# control.net
KiCad netlist of a schematic drawn in EAGLE
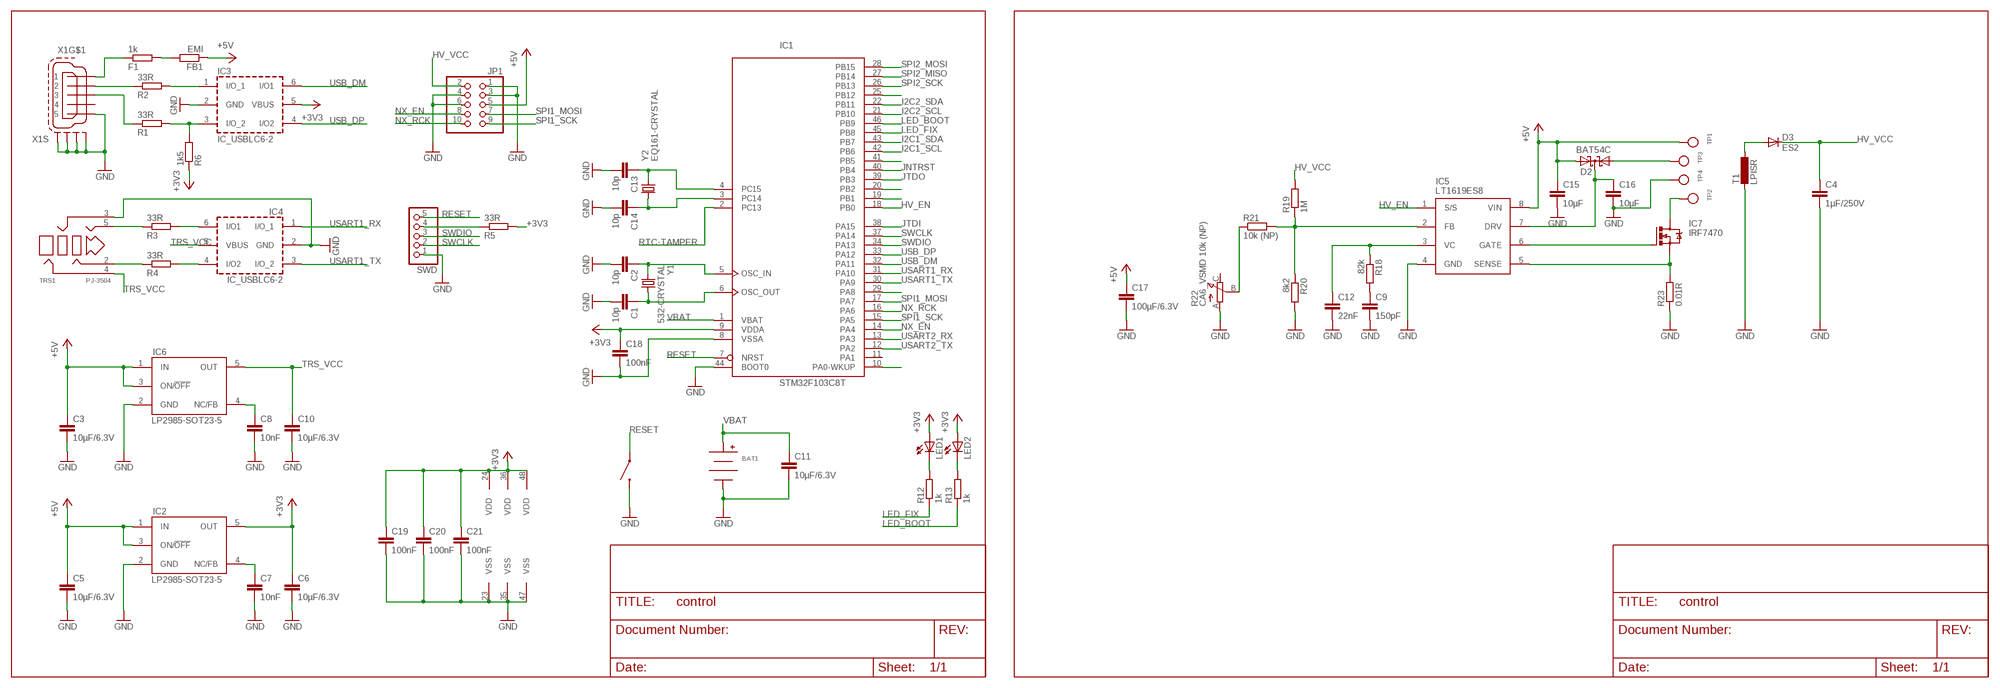
[diagram p0: schematic, sheet 1]

(export (version "E")
  (design (tool "Eeschema 10.0.6"))
  (components
    (comp (ref "BAT1")
      (value "CR1220-HOLDER")
      (footprint "eagle-import:HARWIN-CR1220")
      (libsource (lib "eagle-import") (part "CR1220-HOLDER"))
    )
    (comp (ref "C1")
      (value "10p")
      (footprint "eagle-import:C0603")
      (libsource (lib "eagle-import") (part "C-EUC0603"))
    )
    (comp (ref "C2")
      (value "10p")
      (footprint "eagle-import:C0603")
      (libsource (lib "eagle-import") (part "C-EUC0603"))
    )
    (comp (ref "C3")
      (value "10µF/6.3V")
      (footprint "eagle-import:C0603")
      (libsource (lib "eagle-import") (part "C-EUC0603"))
    )
    (comp (ref "C4")
      (value "1µF/250V")
      (footprint "eagle-import:C2220K")
      (libsource (lib "eagle-import") (part "C-EUC2220K"))
    )
    (comp (ref "C5")
      (value "10µF/6.3V")
      (footprint "eagle-import:C0603")
      (libsource (lib "eagle-import") (part "C-EUC0603"))
    )
    (comp (ref "C6")
      (value "10µF/6.3V")
      (footprint "eagle-import:C0603")
      (libsource (lib "eagle-import") (part "C-EUC0603"))
    )
    (comp (ref "C7")
      (value "10nF")
      (footprint "eagle-import:C0603")
      (libsource (lib "eagle-import") (part "C-EUC0603"))
    )
    (comp (ref "C8")
      (value "10nF")
      (footprint "eagle-import:C0603")
      (libsource (lib "eagle-import") (part "C-EUC0603"))
    )
    (comp (ref "C9")
      (value "150pF")
      (footprint "eagle-import:C0603")
      (libsource (lib "eagle-import") (part "C-EUC0603"))
    )
    (comp (ref "C10")
      (value "10µF/6.3V")
      (footprint "eagle-import:C0603")
      (libsource (lib "eagle-import") (part "C-EUC0603"))
    )
    (comp (ref "C11")
      (value "10µF/6.3V")
      (footprint "eagle-import:C0603")
      (libsource (lib "eagle-import") (part "C-EUC0603"))
    )
    (comp (ref "C12")
      (value "22nF")
      (footprint "eagle-import:C0603")
      (libsource (lib "eagle-import") (part "C-EUC0603"))
    )
    (comp (ref "C13")
      (value "10p")
      (footprint "eagle-import:C0603")
      (libsource (lib "eagle-import") (part "C-EUC0603"))
    )
    (comp (ref "C14")
      (value "10p")
      (footprint "eagle-import:C0603")
      (libsource (lib "eagle-import") (part "C-EUC0603"))
    )
    (comp (ref "C15")
      (value "10µF")
      (footprint "eagle-import:C0603")
      (libsource (lib "eagle-import") (part "C-EUC0603"))
    )
    (comp (ref "C16")
      (value "10µF")
      (footprint "eagle-import:C0603")
      (libsource (lib "eagle-import") (part "C-EUC0603"))
    )
    (comp (ref "C17")
      (value "100µF/6.3V")
      (footprint "eagle-import:C1210")
      (libsource (lib "eagle-import") (part "C-EUC1210"))
    )
    (comp (ref "C18")
      (value "100nF")
      (footprint "eagle-import:C0603")
      (libsource (lib "eagle-import") (part "C-EUC0603"))
    )
    (comp (ref "C19")
      (value "100nF")
      (footprint "eagle-import:C0603")
      (libsource (lib "eagle-import") (part "C-EUC0603"))
    )
    (comp (ref "C20")
      (value "100nF")
      (footprint "eagle-import:C0603")
      (libsource (lib "eagle-import") (part "C-EUC0603"))
    )
    (comp (ref "C21")
      (value "100nF")
      (footprint "eagle-import:C0603")
      (libsource (lib "eagle-import") (part "C-EUC0603"))
    )
    (comp (ref "D2")
      (value "BAT54C")
      (footprint "eagle-import:SOT23")
      (libsource (lib "eagle-import") (part "BAT54C"))
    )
    (comp (ref "D3")
      (value "ES2")
      (footprint "eagle-import:DO-214AA")
      (libsource (lib "eagle-import") (part "ES2"))
    )
    (comp (ref "F1")
      (value "1k")
      (footprint "eagle-import:R0603")
      (libsource (lib "eagle-import") (part "R-EU_R0603"))
    )
    (comp (ref "FB1")
      (value "EMI")
      (footprint "eagle-import:R0603")
      (libsource (lib "eagle-import") (part "R-EU_R0603"))
    )
    (comp (ref "IC1")
      (value "STM32F103C8T")
      (footprint "eagle-import:LQFP48")
      (libsource (lib "eagle-import") (part "STM32F103CT8"))
    )
    (comp (ref "IC2")
      (value "LP2985-SOT23-5")
      (footprint "eagle-import:SOT23-5")
      (libsource (lib "eagle-import") (part "LP2985-SOT23-5"))
    )
    (comp (ref "IC3")
      (value "IC_USBLC6-2")
      (footprint "eagle-import:SOT-23-6L")
      (libsource (lib "eagle-import") (part "IC_USBLC6-2"))
    )
    (comp (ref "IC4")
      (value "IC_USBLC6-2")
      (footprint "eagle-import:SOT-23-6L")
      (libsource (lib "eagle-import") (part "IC_USBLC6-2"))
    )
    (comp (ref "IC5")
      (value "LT1619ES8")
      (footprint "eagle-import:SO8")
      (libsource (lib "eagle-import") (part "LT1619ES8"))
    )
    (comp (ref "IC6")
      (value "LP2985-SOT23-5")
      (footprint "eagle-import:SOT23-5")
      (libsource (lib "eagle-import") (part "LP2985-SOT23-5"))
    )
    (comp (ref "IC7")
      (value "IRF7470")
      (footprint "eagle-import:SO8")
      (libsource (lib "eagle-import") (part "IRF7470"))
    )
    (comp (ref "ISP")
      (value "TACT-SWITCH-40-40")
      (footprint "eagle-import:40-40")
      (libsource (lib "eagle-import") (part "TACT-SWITCH-40-40"))
    )
    (comp (ref "JP1")
      (value "PINHD-2X5_2.54-SMD")
      (footprint "eagle-import:2X05SMD")
      (libsource (lib "eagle-import") (part "PINHD-2X5_2.54-SMD"))
    )
    (comp (ref "LED1")
      (value "LEDCHIP-LED0603")
      (footprint "eagle-import:CHIP-LED0603")
      (libsource (lib "eagle-import") (part "LEDCHIP-LED0603"))
    )
    (comp (ref "LED2")
      (value "LEDCHIP-LED0603")
      (footprint "eagle-import:CHIP-LED0603")
      (libsource (lib "eagle-import") (part "LEDCHIP-LED0603"))
    )
    (comp (ref "R1")
      (value "33R")
      (footprint "eagle-import:R0603")
      (libsource (lib "eagle-import") (part "R-EU_R0603"))
    )
    (comp (ref "R2")
      (value "33R")
      (footprint "eagle-import:R0603")
      (libsource (lib "eagle-import") (part "R-EU_R0603"))
    )
    (comp (ref "R3")
      (value "33R")
      (footprint "eagle-import:R0603")
      (libsource (lib "eagle-import") (part "R-EU_R0603"))
    )
    (comp (ref "R4")
      (value "33R")
      (footprint "eagle-import:R0603")
      (libsource (lib "eagle-import") (part "R-EU_R0603"))
    )
    (comp (ref "R5")
      (value "33R")
      (footprint "eagle-import:R0603")
      (libsource (lib "eagle-import") (part "R-EU_R0603"))
    )
    (comp (ref "R6")
      (value "1k5")
      (footprint "eagle-import:R0603")
      (libsource (lib "eagle-import") (part "R-EU_R0603"))
    )
    (comp (ref "R12")
      (value "1k")
      (footprint "eagle-import:R0603")
      (libsource (lib "eagle-import") (part "R-EU_R0603"))
    )
    (comp (ref "R13")
      (value "1k")
      (footprint "eagle-import:R0603")
      (libsource (lib "eagle-import") (part "R-EU_R0603"))
    )
    (comp (ref "R18")
      (value "82k")
      (footprint "eagle-import:R0603")
      (libsource (lib "eagle-import") (part "R-EU_R0603"))
    )
    (comp (ref "R19")
      (value "1M")
      (footprint "eagle-import:M1206")
      (libsource (lib "eagle-import") (part "R-EU_M1206"))
    )
    (comp (ref "R20")
      (value "8k2")
      (footprint "eagle-import:R0603")
      (libsource (lib "eagle-import") (part "R-EU_R0603"))
    )
    (comp (ref "R21")
      (value "10k (NP)")
      (footprint "eagle-import:R0603")
      (libsource (lib "eagle-import") (part "R-EU_R0603"))
    )
    (comp (ref "R22")
      (value "CA6_VSMD 10k (NP)")
      (footprint "eagle-import:CA6-VSMD")
      (libsource (lib "eagle-import") (part "CA6_VSMD"))
    )
    (comp (ref "R23")
      (value "0.01R")
      (footprint "eagle-import:R1206")
      (libsource (lib "eagle-import") (part "R-EU_R1206"))
    )
    (comp (ref "SWD")
      (value "HEADER-1X5ROUND")
      (footprint "eagle-import:1X05_ROUND")
      (libsource (lib "eagle-import") (part "HEADER-1X5ROUND"))
    )
    (comp (ref "T1")
      (value "LPISR")
      (footprint "eagle-import:PISR")
      (libsource (lib "eagle-import") (part "LPISR"))
    )
    (comp (ref "TP1")
      (value "TESTPOINTROUND2MM")
      (footprint "eagle-import:TESTPOINT_ROUND_2MM")
      (libsource (lib "eagle-import") (part "TESTPOINTROUND2MM"))
    )
    (comp (ref "TP2")
      (value "TESTPOINTROUND2MM")
      (footprint "eagle-import:TESTPOINT_ROUND_2MM")
      (libsource (lib "eagle-import") (part "TESTPOINTROUND2MM"))
    )
    (comp (ref "TP3")
      (value "TESTPOINTROUND2MM")
      (footprint "eagle-import:TESTPOINT_ROUND_2MM")
      (libsource (lib "eagle-import") (part "TESTPOINTROUND2MM"))
    )
    (comp (ref "TP4")
      (value "TESTPOINTROUND2MM")
      (footprint "eagle-import:TESTPOINT_ROUND_2MM")
      (libsource (lib "eagle-import") (part "TESTPOINTROUND2MM"))
    )
    (comp (ref "TRS1")
      (value "PJ-3504")
      (footprint "eagle-import:YD-PJ-3504")
      (libsource (lib "eagle-import") (part "PJ-3504"))
    )
    (comp (ref "X1")
      (value "MINI-USB-SCHIELD-32005-201")
      (footprint "eagle-import:32005-201")
      (libsource (lib "eagle-import") (part "MINI-USB-SCHIELD-32005-201"))
    )
    (comp (ref "Y1")
      (value "532-CRYSTAL")
      (footprint "eagle-import:2PIN50X32")
      (libsource (lib "eagle-import") (part "532-CRYSTAL"))
    )
    (comp (ref "Y2")
      (value "EQ161-CRYSTAL")
      (footprint "eagle-import:EQ161")
      (libsource (lib "eagle-import") (part "EQ161-CRYSTAL"))
    )
  )
  (nets
    (net (code "1") (name "+3V3") (class "Default")
      (node (ref "C18") (pin "1") (pinfunction "1_1") (pintype "passive"))
      (node (ref "C19") (pin "1") (pinfunction "1_1") (pintype "passive"))
      (node (ref "C20") (pin "1") (pinfunction "1_1") (pintype "passive"))
      (node (ref "C21") (pin "1") (pinfunction "1_1") (pintype "passive"))
      (node (ref "C6") (pin "1") (pinfunction "1_1") (pintype "passive"))
      (node (ref "IC1") (pin "24") (pinfunction "VDD_24") (pintype "power_in"))
      (node (ref "IC1") (pin "36") (pinfunction "VDD_36") (pintype "power_in"))
      (node (ref "IC1") (pin "48") (pinfunction "VDD_48") (pintype "power_in"))
      (node (ref "IC1") (pin "9") (pinfunction "VDDA_9") (pintype "power_in"))
      (node (ref "IC2") (pin "5") (pinfunction "OUT_5") (pintype "bidirectional"))
      (node (ref "IC3") (pin "5") (pinfunction "VBUS_5") (pintype "bidirectional"))
      (node (ref "LED1") (pin "A") (pinfunction "A_A") (pintype "passive"))
      (node (ref "LED2") (pin "A") (pinfunction "A_A") (pintype "passive"))
      (node (ref "R5") (pin "2") (pinfunction "2_2") (pintype "passive"))
      (node (ref "R6") (pin "1") (pinfunction "1_1") (pintype "passive"))
    )
    (net (code "2") (name "+5V") (class "Default")
      (node (ref "C15") (pin "1") (pinfunction "1_1") (pintype "passive"))
      (node (ref "C17") (pin "1") (pinfunction "1_1") (pintype "passive"))
      (node (ref "C3") (pin "1") (pinfunction "1_1") (pintype "passive"))
      (node (ref "C5") (pin "1") (pinfunction "1_1") (pintype "passive"))
      (node (ref "D2") (pin "2") (pinfunction "A2_2") (pintype "passive"))
      (node (ref "FB1") (pin "1") (pinfunction "1_1") (pintype "passive"))
      (node (ref "IC2") (pin "1") (pinfunction "IN_1") (pintype "bidirectional"))
      (node (ref "IC2") (pin "3") (pinfunction "ON/~{OFF}_3") (pintype "bidirectional"))
      (node (ref "IC5") (pin "8") (pinfunction "VIN_8") (pintype "bidirectional"))
      (node (ref "IC6") (pin "1") (pinfunction "IN_1") (pintype "bidirectional"))
      (node (ref "IC6") (pin "3") (pinfunction "ON/~{OFF}_3") (pintype "bidirectional"))
      (node (ref "JP1") (pin "5") (pinfunction "5_5") (pintype "passive"))
      (node (ref "TP1") (pin "P$1") (pinfunction "P$1_P$1") (pintype "bidirectional"))
    )
    (net (code "3") (name "/HV_EN") (class "Default")
      (node (ref "IC1") (pin "18") (pinfunction "PB0_18") (pintype "bidirectional"))
      (node (ref "IC5") (pin "1") (pinfunction "S/S_1") (pintype "bidirectional"))
    )
    (net (code "4") (name "/HV_VCC") (class "Default")
      (node (ref "C4") (pin "1") (pinfunction "1_1") (pintype "passive"))
      (node (ref "D3") (pin "C") (pinfunction "C_C") (pintype "passive"))
      (node (ref "JP1") (pin "2") (pinfunction "2_2") (pintype "passive"))
      (node (ref "R19") (pin "2") (pinfunction "2_2") (pintype "passive"))
    )
    (net (code "5") (name "/I2C1_SCL") (class "Default")
      (node (ref "IC1") (pin "42") (pinfunction "PB6_42") (pintype "bidirectional"))
    )
    (net (code "6") (name "/I2C1_SDA") (class "Default")
      (node (ref "IC1") (pin "43") (pinfunction "PB7_43") (pintype "bidirectional"))
    )
    (net (code "7") (name "/I2C2_SCL") (class "Default")
      (node (ref "IC1") (pin "21") (pinfunction "PB10_21") (pintype "bidirectional"))
    )
    (net (code "8") (name "/I2C2_SDA") (class "Default")
      (node (ref "IC1") (pin "22") (pinfunction "PB11_22") (pintype "bidirectional"))
    )
    (net (code "9") (name "/JNTRST") (class "Default")
      (node (ref "IC1") (pin "40") (pinfunction "PB4_40") (pintype "bidirectional"))
    )
    (net (code "10") (name "/JTDI") (class "Default")
      (node (ref "IC1") (pin "38") (pinfunction "PA15_38") (pintype "bidirectional"))
    )
    (net (code "11") (name "/JTDO") (class "Default")
      (node (ref "IC1") (pin "39") (pinfunction "PB3_39") (pintype "bidirectional"))
    )
    (net (code "12") (name "/LED_BOOT") (class "Default")
      (node (ref "IC1") (pin "46") (pinfunction "PB9_46") (pintype "bidirectional"))
      (node (ref "R13") (pin "1") (pinfunction "1_1") (pintype "passive"))
    )
    (net (code "13") (name "/LED_FIX") (class "Default")
      (node (ref "IC1") (pin "45") (pinfunction "PB8_45") (pintype "bidirectional"))
      (node (ref "R12") (pin "1") (pinfunction "1_1") (pintype "passive"))
    )
    (net (code "14") (name "/NX_EN") (class "Default")
      (node (ref "IC1") (pin "14") (pinfunction "PA4_14") (pintype "bidirectional"))
      (node (ref "JP1") (pin "8") (pinfunction "8_8") (pintype "passive"))
    )
    (net (code "15") (name "/NX_RCK") (class "Default")
      (node (ref "IC1") (pin "16") (pinfunction "PA6_16") (pintype "bidirectional"))
      (node (ref "JP1") (pin "10") (pinfunction "10_10") (pintype "passive"))
    )
    (net (code "16") (name "/RESET") (class "Default")
      (node (ref "IC1") (pin "7") (pinfunction "NRST_7") (pintype "bidirectional"))
      (node (ref "ISP") (pin "3") (pinfunction "P$2_3") (pintype "bidirectional"))
      (node (ref "ISP") (pin "4") (pinfunction "P$2_4") (pintype "bidirectional"))
      (node (ref "SWD") (pin "5") (pinfunction "5_5") (pintype "passive"))
    )
    (net (code "17") (name "/RTC-TAMPER") (class "Default")
      (node (ref "IC1") (pin "2") (pinfunction "PC13_2") (pintype "bidirectional"))
    )
    (net (code "18") (name "/SPI1_MOSI") (class "Default")
      (node (ref "IC1") (pin "17") (pinfunction "PA7_17") (pintype "bidirectional"))
      (node (ref "JP1") (pin "7") (pinfunction "7_7") (pintype "passive"))
    )
    (net (code "19") (name "/SPI1_SCK") (class "Default")
      (node (ref "IC1") (pin "15") (pinfunction "PA5_15") (pintype "bidirectional"))
      (node (ref "JP1") (pin "9") (pinfunction "9_9") (pintype "passive"))
    )
    (net (code "20") (name "/SPI2_MISO") (class "Default")
      (node (ref "IC1") (pin "27") (pinfunction "PB14_27") (pintype "bidirectional"))
    )
    (net (code "21") (name "/SPI2_MOSI") (class "Default")
      (node (ref "IC1") (pin "28") (pinfunction "PB15_28") (pintype "bidirectional"))
    )
    (net (code "22") (name "/SPI2_SCK") (class "Default")
      (node (ref "IC1") (pin "26") (pinfunction "PB13_26") (pintype "bidirectional"))
    )
    (net (code "23") (name "/SWCLK") (class "Default")
      (node (ref "IC1") (pin "37") (pinfunction "PA14_37") (pintype "bidirectional"))
      (node (ref "SWD") (pin "2") (pinfunction "2_2") (pintype "passive"))
    )
    (net (code "24") (name "/SWDIO") (class "Default")
      (node (ref "IC1") (pin "34") (pinfunction "PA13_34") (pintype "bidirectional"))
      (node (ref "SWD") (pin "3") (pinfunction "3_3") (pintype "passive"))
    )
    (net (code "25") (name "/TRS_VCC") (class "Default")
      (node (ref "C10") (pin "1") (pinfunction "1_1") (pintype "passive"))
      (node (ref "IC4") (pin "5") (pinfunction "VBUS_5") (pintype "bidirectional"))
      (node (ref "IC6") (pin "5") (pinfunction "OUT_5") (pintype "bidirectional"))
      (node (ref "TRS1") (pin "4") (pinfunction "4_4") (pintype "bidirectional"))
    )
    (net (code "26") (name "/USART1_RX") (class "Default")
      (node (ref "IC1") (pin "31") (pinfunction "PA10_31") (pintype "bidirectional"))
      (node (ref "IC4") (pin "1") (pinfunction "I/O_1_1") (pintype "bidirectional"))
    )
    (net (code "27") (name "/USART1_TX") (class "Default")
      (node (ref "IC1") (pin "30") (pinfunction "PA9_30") (pintype "bidirectional"))
      (node (ref "IC4") (pin "3") (pinfunction "I/O_2_3") (pintype "bidirectional"))
    )
    (net (code "28") (name "/USART2_RX") (class "Default")
      (node (ref "IC1") (pin "13") (pinfunction "PA3_13") (pintype "bidirectional"))
    )
    (net (code "29") (name "/USART2_TX") (class "Default")
      (node (ref "IC1") (pin "12") (pinfunction "PA2_12") (pintype "bidirectional"))
    )
    (net (code "30") (name "/USB_DM") (class "Default")
      (node (ref "IC1") (pin "32") (pinfunction "PA11_32") (pintype "bidirectional"))
      (node (ref "IC3") (pin "6") (pinfunction "I/O1_6") (pintype "bidirectional"))
    )
    (net (code "31") (name "/USB_DP") (class "Default")
      (node (ref "IC1") (pin "33") (pinfunction "PA12_33") (pintype "bidirectional"))
      (node (ref "IC3") (pin "4") (pinfunction "I/O2_4") (pintype "bidirectional"))
    )
    (net (code "32") (name "/VBAT") (class "Default")
      (node (ref "BAT1") (pin "POS") (pinfunction "POS_POS") (pintype "bidirectional"))
      (node (ref "C11") (pin "1") (pinfunction "1_1") (pintype "passive"))
      (node (ref "IC1") (pin "1") (pinfunction "VBAT_1") (pintype "power_in"))
    )
    (net (code "33") (name "GND") (class "Default")
      (node (ref "BAT1") (pin "NEG") (pinfunction "NEG_NEG") (pintype "bidirectional"))
      (node (ref "C1") (pin "2") (pinfunction "2_2") (pintype "passive"))
      (node (ref "C10") (pin "2") (pinfunction "2_2") (pintype "passive"))
      (node (ref "C11") (pin "2") (pinfunction "2_2") (pintype "passive"))
      (node (ref "C12") (pin "2") (pinfunction "2_2") (pintype "passive"))
      (node (ref "C13") (pin "2") (pinfunction "2_2") (pintype "passive"))
      (node (ref "C14") (pin "2") (pinfunction "2_2") (pintype "passive"))
      (node (ref "C15") (pin "2") (pinfunction "2_2") (pintype "passive"))
      (node (ref "C16") (pin "2") (pinfunction "2_2") (pintype "passive"))
      (node (ref "C17") (pin "2") (pinfunction "2_2") (pintype "passive"))
      (node (ref "C18") (pin "2") (pinfunction "2_2") (pintype "passive"))
      (node (ref "C19") (pin "2") (pinfunction "2_2") (pintype "passive"))
      (node (ref "C2") (pin "2") (pinfunction "2_2") (pintype "passive"))
      (node (ref "C20") (pin "2") (pinfunction "2_2") (pintype "passive"))
      (node (ref "C21") (pin "2") (pinfunction "2_2") (pintype "passive"))
      (node (ref "C3") (pin "2") (pinfunction "2_2") (pintype "passive"))
      (node (ref "C4") (pin "2") (pinfunction "2_2") (pintype "passive"))
      (node (ref "C5") (pin "2") (pinfunction "2_2") (pintype "passive"))
      (node (ref "C6") (pin "2") (pinfunction "2_2") (pintype "passive"))
      (node (ref "C7") (pin "2") (pinfunction "2_2") (pintype "passive"))
      (node (ref "C8") (pin "2") (pinfunction "2_2") (pintype "passive"))
      (node (ref "C9") (pin "2") (pinfunction "2_2") (pintype "passive"))
      (node (ref "IC1") (pin "23") (pinfunction "VSS_23") (pintype "power_in"))
      (node (ref "IC1") (pin "35") (pinfunction "VSS_35") (pintype "power_in"))
      (node (ref "IC1") (pin "44") (pinfunction "BOOT0_44") (pintype "input"))
      (node (ref "IC1") (pin "47") (pinfunction "VSS_47") (pintype "power_in"))
      (node (ref "IC1") (pin "8") (pinfunction "VSSA_8") (pintype "power_in"))
      (node (ref "IC2") (pin "2") (pinfunction "GND_2") (pintype "bidirectional"))
      (node (ref "IC3") (pin "2") (pinfunction "GND_2") (pintype "bidirectional"))
      (node (ref "IC4") (pin "2") (pinfunction "GND_2") (pintype "bidirectional"))
      (node (ref "IC5") (pin "4") (pinfunction "GND_4") (pintype "bidirectional"))
      (node (ref "IC6") (pin "2") (pinfunction "GND_2") (pintype "bidirectional"))
      (node (ref "ISP") (pin "1") (pinfunction "P$1_1") (pintype "bidirectional"))
      (node (ref "ISP") (pin "2") (pinfunction "P$1_2") (pintype "bidirectional"))
      (node (ref "JP1") (pin "1") (pinfunction "1_1") (pintype "passive"))
      (node (ref "JP1") (pin "3") (pinfunction "3_3") (pintype "passive"))
      (node (ref "JP1") (pin "4") (pinfunction "4_4") (pintype "passive"))
      (node (ref "JP1") (pin "6") (pinfunction "6_6") (pintype "passive"))
      (node (ref "R20") (pin "2") (pinfunction "2_2") (pintype "passive"))
      (node (ref "R22") (pin "A") (pinfunction "A_A") (pintype "passive"))
      (node (ref "R23") (pin "1") (pinfunction "1_1") (pintype "passive"))
      (node (ref "SWD") (pin "1") (pinfunction "1_1") (pintype "passive"))
      (node (ref "T1") (pin "P$2") (pinfunction "2_P$2") (pintype "passive"))
      (node (ref "TP4") (pin "P$1") (pinfunction "P$1_P$1") (pintype "bidirectional"))
      (node (ref "TRS1") (pin "3") (pinfunction "3_3") (pintype "bidirectional"))
      (node (ref "X1") (pin "5") (pinfunction "5_5") (pintype "passive"))
      (node (ref "X1") (pin "M1") (pinfunction "S1_M1") (pintype "passive"))
      (node (ref "X1") (pin "M2") (pinfunction "S2_M2") (pintype "passive"))
      (node (ref "X1") (pin "M3") (pinfunction "S3_M3") (pintype "passive"))
      (node (ref "X1") (pin "M4") (pinfunction "S4_M4") (pintype "passive"))
    )
    (net (code "34") (name "Net-(C9-Pad1)") (class "Default")
      (node (ref "C9") (pin "1") (pinfunction "1_1") (pintype "passive"))
      (node (ref "R18") (pin "2") (pinfunction "2_2") (pintype "passive"))
    )
    (net (code "35") (name "Net-(D2-A1)") (class "Default")
      (node (ref "D2") (pin "1") (pinfunction "A1_1") (pintype "passive"))
      (node (ref "TP3") (pin "P$1") (pinfunction "P$1_P$1") (pintype "bidirectional"))
    )
    (net (code "36") (name "Net-(D2-CC)") (class "Default")
      (node (ref "C16") (pin "1") (pinfunction "1_1") (pintype "passive"))
      (node (ref "D2") (pin "3") (pinfunction "CC_3") (pintype "passive"))
      (node (ref "IC5") (pin "7") (pinfunction "DRV_7") (pintype "bidirectional"))
    )
    (net (code "37") (name "Net-(F1-Pad1)") (class "Default")
      (node (ref "F1") (pin "1") (pinfunction "1_1") (pintype "passive"))
      (node (ref "X1") (pin "1") (pinfunction "1_1") (pintype "passive"))
    )
    (net (code "38") (name "Net-(F1-Pad2)") (class "Default")
      (node (ref "F1") (pin "2") (pinfunction "2_2") (pintype "passive"))
      (node (ref "FB1") (pin "2") (pinfunction "2_2") (pintype "passive"))
    )
    (net (code "39") (name "Net-(IC1A-OSC_IN)") (class "Default")
      (node (ref "C2") (pin "1") (pinfunction "1_1") (pintype "passive"))
      (node (ref "IC1") (pin "5") (pinfunction "OSC_IN_5") (pintype "bidirectional"))
      (node (ref "Y1") (pin "P$2") (pinfunction "2_P$2") (pintype "passive"))
    )
    (net (code "40") (name "Net-(IC1A-OSC_OUT)") (class "Default")
      (node (ref "C1") (pin "1") (pinfunction "1_1") (pintype "passive"))
      (node (ref "IC1") (pin "6") (pinfunction "OSC_OUT_6") (pintype "bidirectional"))
      (node (ref "Y1") (pin "P$1") (pinfunction "1_P$1") (pintype "passive"))
    )
    (net (code "41") (name "Net-(IC1A-PC14)") (class "Default")
      (node (ref "C14") (pin "1") (pinfunction "1_1") (pintype "passive"))
      (node (ref "IC1") (pin "3") (pinfunction "PC14_3") (pintype "bidirectional"))
      (node (ref "Y2") (pin "P$2") (pinfunction "2_P$2") (pintype "passive"))
    )
    (net (code "42") (name "Net-(IC1A-PC15)") (class "Default")
      (node (ref "C13") (pin "1") (pinfunction "1_1") (pintype "passive"))
      (node (ref "IC1") (pin "4") (pinfunction "PC15_4") (pintype "bidirectional"))
      (node (ref "Y2") (pin "P$1") (pinfunction "1_P$1") (pintype "passive"))
    )
    (net (code "43") (name "Net-(IC2-NC{slash}FB)") (class "Default")
      (node (ref "C7") (pin "1") (pinfunction "1_1") (pintype "passive"))
      (node (ref "IC2") (pin "4") (pinfunction "NC/FB_4") (pintype "bidirectional"))
    )
    (net (code "44") (name "Net-(IC3-I{slash}O_1)") (class "Default")
      (node (ref "IC3") (pin "1") (pinfunction "I/O_1_1") (pintype "bidirectional"))
      (node (ref "R2") (pin "2") (pinfunction "2_2") (pintype "passive"))
    )
    (net (code "45") (name "Net-(IC3-I{slash}O_2)") (class "Default")
      (node (ref "IC3") (pin "3") (pinfunction "I/O_2_3") (pintype "bidirectional"))
      (node (ref "R1") (pin "2") (pinfunction "2_2") (pintype "passive"))
      (node (ref "R6") (pin "2") (pinfunction "2_2") (pintype "passive"))
    )
    (net (code "46") (name "Net-(IC4-I{slash}O1)") (class "Default")
      (node (ref "IC4") (pin "6") (pinfunction "I/O1_6") (pintype "bidirectional"))
      (node (ref "R3") (pin "2") (pinfunction "2_2") (pintype "passive"))
    )
    (net (code "47") (name "Net-(IC4-I{slash}O2)") (class "Default")
      (node (ref "IC4") (pin "4") (pinfunction "I/O2_4") (pintype "bidirectional"))
      (node (ref "R4") (pin "2") (pinfunction "2_2") (pintype "passive"))
    )
    (net (code "48") (name "Net-(IC5-FB)") (class "Default")
      (node (ref "IC5") (pin "2") (pinfunction "FB_2") (pintype "bidirectional"))
      (node (ref "R19") (pin "1") (pinfunction "1_1") (pintype "passive"))
      (node (ref "R20") (pin "1") (pinfunction "1_1") (pintype "passive"))
      (node (ref "R21") (pin "2") (pinfunction "2_2") (pintype "passive"))
    )
    (net (code "49") (name "Net-(IC5-GATE)") (class "Default")
      (node (ref "IC5") (pin "6") (pinfunction "GATE_6") (pintype "bidirectional"))
      (node (ref "IC7") (pin "4") (pinfunction "G_4") (pintype "passive"))
    )
    (net (code "50") (name "Net-(IC5-SENSE)") (class "Default")
      (node (ref "IC5") (pin "5") (pinfunction "SENSE_5") (pintype "bidirectional"))
      (node (ref "IC7") (pin "1") (pinfunction "S_1") (pintype "passive"))
      (node (ref "IC7") (pin "2") (pinfunction "S_2") (pintype "passive"))
      (node (ref "IC7") (pin "3") (pinfunction "S_3") (pintype "passive"))
      (node (ref "R23") (pin "2") (pinfunction "2_2") (pintype "passive"))
    )
    (net (code "51") (name "Net-(IC5-VC)") (class "Default")
      (node (ref "C12") (pin "1") (pinfunction "1_1") (pintype "passive"))
      (node (ref "IC5") (pin "3") (pinfunction "VC_3") (pintype "bidirectional"))
      (node (ref "R18") (pin "1") (pinfunction "1_1") (pintype "passive"))
    )
    (net (code "52") (name "Net-(IC6-NC{slash}FB)") (class "Default")
      (node (ref "C8") (pin "1") (pinfunction "1_1") (pintype "passive"))
      (node (ref "IC6") (pin "4") (pinfunction "NC/FB_4") (pintype "bidirectional"))
    )
    (net (code "53") (name "Net-(IC7-D-Pad5)") (class "Default")
      (node (ref "IC7") (pin "5") (pinfunction "D_5") (pintype "passive"))
      (node (ref "IC7") (pin "6") (pinfunction "D_6") (pintype "passive"))
      (node (ref "IC7") (pin "7") (pinfunction "D_7") (pintype "passive"))
      (node (ref "IC7") (pin "8") (pinfunction "D_8") (pintype "passive"))
      (node (ref "TP2") (pin "P$1") (pinfunction "P$1_P$1") (pintype "bidirectional"))
    )
    (net (code "54") (name "Net-(LED1-PadC)") (class "Default")
      (node (ref "LED1") (pin "C") (pinfunction "C_C") (pintype "passive"))
      (node (ref "R12") (pin "2") (pinfunction "2_2") (pintype "passive"))
    )
    (net (code "55") (name "Net-(LED2-PadC)") (class "Default")
      (node (ref "LED2") (pin "C") (pinfunction "C_C") (pintype "passive"))
      (node (ref "R13") (pin "2") (pinfunction "2_2") (pintype "passive"))
    )
    (net (code "56") (name "Net-(R1-Pad1)") (class "Default")
      (node (ref "R1") (pin "1") (pinfunction "1_1") (pintype "passive"))
      (node (ref "X1") (pin "3") (pinfunction "3_3") (pintype "passive"))
    )
    (net (code "57") (name "Net-(R2-Pad1)") (class "Default")
      (node (ref "R2") (pin "1") (pinfunction "1_1") (pintype "passive"))
      (node (ref "X1") (pin "2") (pinfunction "2_2") (pintype "passive"))
    )
    (net (code "58") (name "Net-(R3-Pad1)") (class "Default")
      (node (ref "R3") (pin "1") (pinfunction "1_1") (pintype "passive"))
      (node (ref "TRS1") (pin "5") (pinfunction "5_5") (pintype "bidirectional"))
    )
    (net (code "59") (name "Net-(R4-Pad1)") (class "Default")
      (node (ref "R4") (pin "1") (pinfunction "1_1") (pintype "passive"))
      (node (ref "TRS1") (pin "2") (pinfunction "2_2") (pintype "bidirectional"))
    )
    (net (code "60") (name "Net-(R5-Pad1)") (class "Default")
      (node (ref "R5") (pin "1") (pinfunction "1_1") (pintype "passive"))
      (node (ref "SWD") (pin "4") (pinfunction "4_4") (pintype "passive"))
    )
    (net (code "61") (name "Net-(R22-S)") (class "Default")
      (node (ref "R21") (pin "1") (pinfunction "1_1") (pintype "passive"))
      (node (ref "R22") (pin "B") (pinfunction "S_B") (pintype "passive"))
    )
    (net (code "62") (name "Net-(T1-1)") (class "Default")
      (node (ref "D3") (pin "A") (pinfunction "A_A") (pintype "passive"))
      (node (ref "T1") (pin "P$1") (pinfunction "1_P$1") (pintype "passive"))
    )
    (net (code "63") (name "unconnected-(IC1A-PA0-WKUP-Pad10)") (class "Default")
      (node (ref "IC1") (pin "10") (pinfunction "PA0-WKUP_10") (pintype "bidirectional"))
    )
    (net (code "64") (name "unconnected-(IC1A-PA1-Pad11)") (class "Default")
      (node (ref "IC1") (pin "11") (pinfunction "PA1_11") (pintype "bidirectional"))
    )
    (net (code "65") (name "unconnected-(IC1A-PA8-Pad29)") (class "Default")
      (node (ref "IC1") (pin "29") (pinfunction "PA8_29") (pintype "bidirectional"))
    )
    (net (code "66") (name "unconnected-(IC1A-PB1-Pad19)") (class "Default")
      (node (ref "IC1") (pin "19") (pinfunction "PB1_19") (pintype "bidirectional"))
    )
    (net (code "67") (name "unconnected-(IC1A-PB2-Pad20)") (class "Default")
      (node (ref "IC1") (pin "20") (pinfunction "PB2_20") (pintype "bidirectional"))
    )
    (net (code "68") (name "unconnected-(IC1A-PB5-Pad41)") (class "Default")
      (node (ref "IC1") (pin "41") (pinfunction "PB5_41") (pintype "bidirectional"))
    )
    (net (code "69") (name "unconnected-(IC1A-PB12-Pad25)") (class "Default")
      (node (ref "IC1") (pin "25") (pinfunction "PB12_25") (pintype "bidirectional"))
    )
    (net (code "70") (name "unconnected-(R22-E-PadC)") (class "Default")
      (node (ref "R22") (pin "C") (pinfunction "E_C") (pintype "passive"))
    )
    (net (code "71") (name "unconnected-(X1-Pad4)") (class "Default")
      (node (ref "X1") (pin "4") (pinfunction "4_4") (pintype "passive"))
    )
  )
)
